# drvoutput0.net
KiCad netlist of a schematic drawn in Altium Designer
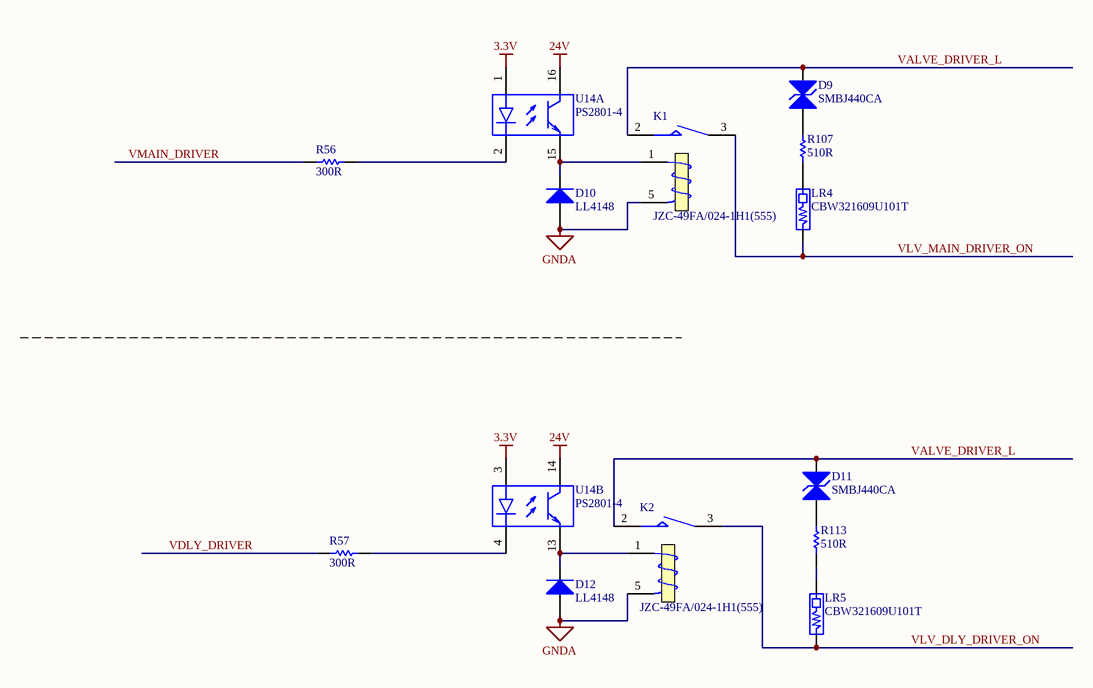
[diagram p0: drvoutput0.SchDoc]

(export (version "E")
  (design (tool "Eeschema 10.0.6"))
  (components
    (comp (ref "D9")
      (value "SMBJ440CA")
      (footprint "SMB")
      (description "Bi-dir TVS Diode")
      (fields (field (name "PUBLISHER") "Altium Limited"))
      (libsource (lib "UserLib") (part "Bi-dir TVS Diode"))
    )
    (comp (ref "D10")
      (value "LL4148")
      (footprint "CD2012-0805")
      (description "1 Amp General Purpose Rectifier")
      (fields (field (name "PUBLISHER") "Altium Limited"))
      (libsource (lib "Miscellaneous Devices") (part "Diode 1N4007"))
    )
    (comp (ref "D11")
      (value "SMBJ440CA")
      (footprint "SMB")
      (description "Bi-dir TVS Diode")
      (fields (field (name "PUBLISHER") "Altium Limited"))
      (libsource (lib "UserLib") (part "Bi-dir TVS Diode"))
    )
    (comp (ref "D12")
      (value "LL4148")
      (footprint "CD2012-0805")
      (description "1 Amp General Purpose Rectifier")
      (fields (field (name "PUBLISHER") "Altium Limited"))
      (libsource (lib "Miscellaneous Devices") (part "Diode 1N4007"))
    )
    (comp (ref "K1")
      (value "JZC-49FA/024-1H1(555)")
      (footprint "JZC-49FA")
      (description "Intermediate  Power  Relay")
      (fields (field (name "PUBLISHER") "Altium Limited"))
      (libsource (lib "UserSchDev") (part "JZC-49FA"))
    )
    (comp (ref "K2")
      (value "JZC-49FA/024-1H1(555)")
      (footprint "JZC-49FA")
      (description "Intermediate  Power  Relay")
      (fields (field (name "PUBLISHER") "Altium Limited"))
      (libsource (lib "UserSchDev") (part "JZC-49FA"))
    )
    (comp (ref "LR4")
      (value "CBW321609U101T")
      (footprint "INDC3216M")
      (description "EMI FILTERS,DC Resistance max.0.05~1.5 ohms,10 ~ 1000 ohms at 100MHz  Frequency")
      (libsource (lib "UserLib") (part "BLM10/11/21/31/41"))
    )
    (comp (ref "LR5")
      (value "CBW321609U101T")
      (footprint "INDC3216M")
      (description "EMI FILTERS,DC Resistance max.0.05~1.5 ohms,10 ~ 1000 ohms at 100MHz  Frequency")
      (libsource (lib "UserLib") (part "BLM10/11/21/31/41"))
    )
    (comp (ref "R56")
      (value "300R")
      (footprint "RESC2012M")
      (description "Resistor")
      (fields (field (name "PUBLISHER") "Altium Limited"))
      (libsource (lib "Miscellaneous Devices") (part "Res1"))
    )
    (comp (ref "R57")
      (value "300R")
      (footprint "RESC2012M")
      (description "Resistor")
      (fields (field (name "PUBLISHER") "Altium Limited"))
      (libsource (lib "Miscellaneous Devices") (part "Res1"))
    )
    (comp (ref "R107")
      (value "510R")
      (footprint "RESC3216M")
      (description "Metal film Resistor")
      (fields (field (name "PUBLISHER") "Altium Limited"))
      (libsource (lib "Miscellaneous Devices") (part "Res1"))
    )
    (comp (ref "R113")
      (value "510R")
      (footprint "RESC3216M")
      (description "Metal film Resistor")
      (fields (field (name "PUBLISHER") "Altium Limited"))
      (libsource (lib "Miscellaneous Devices") (part "Res1"))
    )
    (comp (ref "U14")
      (value "PS2801-4")
      (footprint "SOIC16_N")
      (fields (field (name "PUBLISHER") "Altium Limited"))
      (libsource (lib "UserSchDev") (part "PS2801-4"))
    )
  )
  (nets
    (net (code "1") (name "/VALVE_DRIVER_L") (class "Default")
      (node (ref "D11") (pin "2") (pinfunction "K_2") (pintype "passive"))
      (node (ref "D9") (pin "2") (pinfunction "K_2") (pintype "passive"))
      (node (ref "K1") (pin "2") (pinfunction "COM_2") (pintype "passive"))
      (node (ref "K2") (pin "2") (pinfunction "COM_2") (pintype "passive"))
    )
    (net (code "2") (name "/VDLY_DRIVER") (class "Default")
      (node (ref "R57") (pin "1") (pinfunction "1_1") (pintype "passive"))
    )
    (net (code "3") (name "/VLV_DLY_DRIVER_ON") (class "Default")
      (node (ref "K2") (pin "3") (pinfunction "NO_3") (pintype "passive"))
      (node (ref "LR5") (pin "1") (pinfunction "1_1") (pintype "passive"))
    )
    (net (code "4") (name "/VLV_MAIN_DRIVER_ON") (class "Default")
      (node (ref "K1") (pin "3") (pinfunction "NO_3") (pintype "passive"))
      (node (ref "LR4") (pin "1") (pinfunction "1_1") (pintype "passive"))
    )
    (net (code "5") (name "/VMAIN_DRIVER") (class "Default")
      (node (ref "R56") (pin "1") (pinfunction "1_1") (pintype "passive"))
    )
    (net (code "6") (name "3.3V") (class "Default")
      (node (ref "U14") (pin "1") (pinfunction "+_1") (pintype "passive"))
      (node (ref "U14") (pin "3") (pinfunction "+_3") (pintype "passive"))
    )
    (net (code "7") (name "24V") (class "Default")
      (node (ref "U14") (pin "14") (pinfunction "C_14") (pintype "passive"))
      (node (ref "U14") (pin "16") (pinfunction "C_16") (pintype "passive"))
    )
    (net (code "8") (name "GNDA") (class "Default")
      (node (ref "D10") (pin "1") (pinfunction "A_1") (pintype "passive"))
      (node (ref "D12") (pin "1") (pinfunction "A_1") (pintype "passive"))
      (node (ref "K1") (pin "5") (pinfunction "T2_5") (pintype "passive"))
      (node (ref "K2") (pin "5") (pinfunction "T2_5") (pintype "passive"))
    )
    (net (code "9") (name "Net-(D9-A)") (class "Default")
      (node (ref "D9") (pin "1") (pinfunction "A_1") (pintype "passive"))
      (node (ref "R107") (pin "2") (pinfunction "2_2") (pintype "passive"))
    )
    (net (code "10") (name "Net-(D10-K)") (class "Default")
      (node (ref "D10") (pin "2") (pinfunction "K_2") (pintype "passive"))
      (node (ref "K1") (pin "1") (pinfunction "1_1") (pintype "passive"))
      (node (ref "U14") (pin "15") (pinfunction "E_15") (pintype "passive"))
    )
    (net (code "11") (name "Net-(D11-A)") (class "Default")
      (node (ref "D11") (pin "1") (pinfunction "A_1") (pintype "passive"))
      (node (ref "R113") (pin "2") (pinfunction "2_2") (pintype "passive"))
    )
    (net (code "12") (name "Net-(D12-K)") (class "Default")
      (node (ref "D12") (pin "2") (pinfunction "K_2") (pintype "passive"))
      (node (ref "K2") (pin "1") (pinfunction "1_1") (pintype "passive"))
      (node (ref "U14") (pin "13") (pinfunction "E_13") (pintype "passive"))
    )
    (net (code "13") (name "Net-(LR4-Pad2)") (class "Default")
      (node (ref "LR4") (pin "2") (pinfunction "2_2") (pintype "passive"))
      (node (ref "R107") (pin "1") (pinfunction "1_1") (pintype "passive"))
    )
    (net (code "14") (name "Net-(LR5-Pad2)") (class "Default")
      (node (ref "LR5") (pin "2") (pinfunction "2_2") (pintype "passive"))
      (node (ref "R113") (pin "1") (pinfunction "1_1") (pintype "passive"))
    )
    (net (code "15") (name "Net-(U14A--)") (class "Default")
      (node (ref "R56") (pin "2") (pinfunction "2_2") (pintype "passive"))
      (node (ref "U14") (pin "2") (pinfunction "-_2") (pintype "passive"))
    )
    (net (code "16") (name "Net-(U14B--)") (class "Default")
      (node (ref "R57") (pin "2") (pinfunction "2_2") (pintype "passive"))
      (node (ref "U14") (pin "4") (pinfunction "-_4") (pintype "passive"))
    )
  )
)
